# LFR_IR.net
KiCad netlist of a schematic drawn in Altium Designer
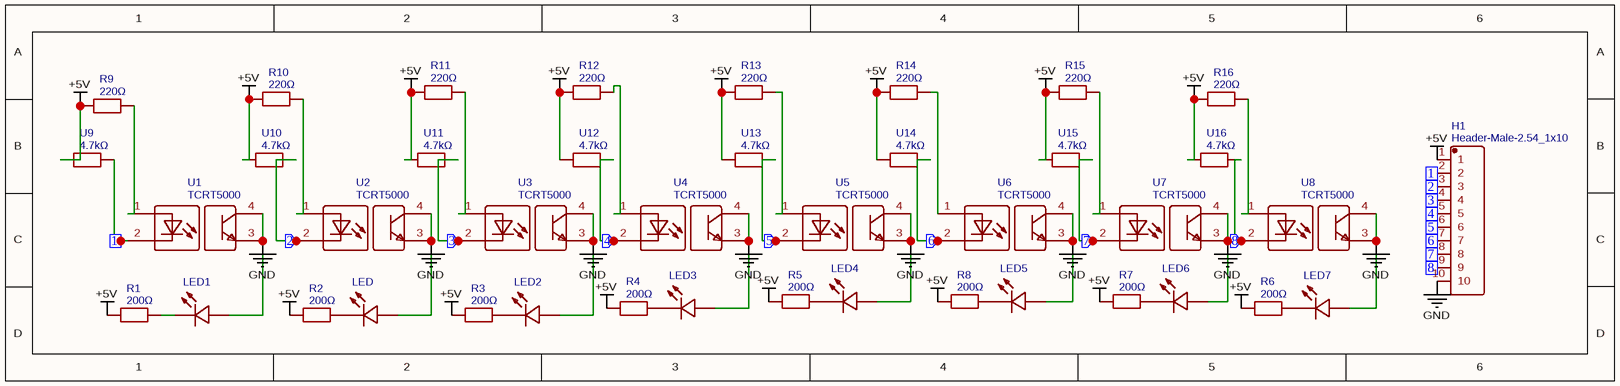
[diagram p0: LFR_IR.schdoc]

(export (version "E")
  (design (tool "Eeschema 10.0.6"))
  (components
    (comp (ref "H1")
      (value "Header-Male-2.54_1x10")
      (fields (field (name "MANUFACTURER PART") "2.54-1*10P针") (field (name "MANUFACTURER") "BOOMELE(博穆精密)"))
      (libsource (lib "altium-import") (part "root_0_Header-Male-2.54_1x10_"))
    )
    (comp (ref "LED")
      (value "LED-2835-白")
      (fields (field (name "CONTRIBUTOR") "LCSC"))
      (libsource (lib "altium-import") (part "root_0_LED-2835-白_"))
    )
    (comp (ref "LED1")
      (value "LED-2835-白")
      (fields (field (name "CONTRIBUTOR") "LCSC"))
      (libsource (lib "altium-import") (part "root_0_LED-2835-白_"))
    )
    (comp (ref "LED2")
      (value "LED-2835-白")
      (fields (field (name "CONTRIBUTOR") "LCSC"))
      (libsource (lib "altium-import") (part "root_0_LED-2835-白_"))
    )
    (comp (ref "LED3")
      (value "LED-2835-白")
      (fields (field (name "CONTRIBUTOR") "LCSC"))
      (libsource (lib "altium-import") (part "root_0_LED-2835-白_"))
    )
    (comp (ref "LED4")
      (value "LED-2835-白")
      (fields (field (name "CONTRIBUTOR") "LCSC"))
      (libsource (lib "altium-import") (part "root_0_LED-2835-白_"))
    )
    (comp (ref "LED5")
      (value "LED-2835-白")
      (fields (field (name "CONTRIBUTOR") "LCSC"))
      (libsource (lib "altium-import") (part "root_0_LED-2835-白_"))
    )
    (comp (ref "LED6")
      (value "LED-2835-白")
      (fields (field (name "CONTRIBUTOR") "LCSC"))
      (libsource (lib "altium-import") (part "root_0_LED-2835-白_"))
    )
    (comp (ref "LED7")
      (value "LED-2835-白")
      (fields (field (name "CONTRIBUTOR") "LCSC"))
      (libsource (lib "altium-import") (part "root_0_LED-2835-白_"))
    )
    (comp (ref "R1")
      (value "200Ω")
      (fields
        (field (name "MANUFACTURER") "VO(翔胜)")
        (field (name "MANUFACTURER PART") "CR1/4W-200Ω±5%-ST52")
        (field (name "CONTRIBUTOR") "lcsc")
      )
      (libsource (lib "altium-import") (part "root_0_200Ω_"))
    )
    (comp (ref "R2")
      (value "200Ω")
      (fields
        (field (name "MANUFACTURER") "VO(翔胜)")
        (field (name "MANUFACTURER PART") "CR1/4W-200Ω±5%-ST52")
        (field (name "CONTRIBUTOR") "lcsc")
      )
      (libsource (lib "altium-import") (part "root_0_200Ω_"))
    )
    (comp (ref "R3")
      (value "200Ω")
      (fields
        (field (name "MANUFACTURER") "VO(翔胜)")
        (field (name "MANUFACTURER PART") "CR1/4W-200Ω±5%-ST52")
        (field (name "CONTRIBUTOR") "lcsc")
      )
      (libsource (lib "altium-import") (part "root_0_200Ω_"))
    )
    (comp (ref "R4")
      (value "200Ω")
      (fields
        (field (name "MANUFACTURER") "VO(翔胜)")
        (field (name "MANUFACTURER PART") "CR1/4W-200Ω±5%-ST52")
        (field (name "CONTRIBUTOR") "lcsc")
      )
      (libsource (lib "altium-import") (part "root_0_200Ω_"))
    )
    (comp (ref "R5")
      (value "200Ω")
      (fields
        (field (name "MANUFACTURER") "VO(翔胜)")
        (field (name "MANUFACTURER PART") "CR1/4W-200Ω±5%-ST52")
        (field (name "CONTRIBUTOR") "lcsc")
      )
      (libsource (lib "altium-import") (part "root_0_200Ω_"))
    )
    (comp (ref "R6")
      (value "200Ω")
      (fields
        (field (name "MANUFACTURER") "VO(翔胜)")
        (field (name "MANUFACTURER PART") "CR1/4W-200Ω±5%-ST52")
        (field (name "CONTRIBUTOR") "lcsc")
      )
      (libsource (lib "altium-import") (part "root_0_200Ω_"))
    )
    (comp (ref "R7")
      (value "200Ω")
      (fields
        (field (name "MANUFACTURER") "VO(翔胜)")
        (field (name "MANUFACTURER PART") "CR1/4W-200Ω±5%-ST52")
        (field (name "CONTRIBUTOR") "lcsc")
      )
      (libsource (lib "altium-import") (part "root_0_200Ω_"))
    )
    (comp (ref "R8")
      (value "200Ω")
      (fields
        (field (name "MANUFACTURER") "VO(翔胜)")
        (field (name "MANUFACTURER PART") "CR1/4W-200Ω±5%-ST52")
        (field (name "CONTRIBUTOR") "lcsc")
      )
      (libsource (lib "altium-import") (part "root_0_200Ω_"))
    )
    (comp (ref "R9")
      (value "220Ω")
      (fields
        (field (name "MANUFACTURER") "VO(翔胜)")
        (field (name "MANUFACTURER PART") "CR1/4W-220Ω±5%-ST52")
        (field (name "CONTRIBUTOR") "lcsc")
      )
      (libsource (lib "altium-import") (part "root_0_220Ω_"))
    )
    (comp (ref "R10")
      (value "220Ω")
      (fields
        (field (name "MANUFACTURER") "VO(翔胜)")
        (field (name "MANUFACTURER PART") "CR1/4W-220Ω±5%-ST52")
        (field (name "CONTRIBUTOR") "lcsc")
      )
      (libsource (lib "altium-import") (part "root_0_220Ω_"))
    )
    (comp (ref "R11")
      (value "220Ω")
      (fields
        (field (name "MANUFACTURER") "VO(翔胜)")
        (field (name "MANUFACTURER PART") "CR1/4W-220Ω±5%-ST52")
        (field (name "CONTRIBUTOR") "lcsc")
      )
      (libsource (lib "altium-import") (part "root_0_220Ω_"))
    )
    (comp (ref "R12")
      (value "220Ω")
      (fields
        (field (name "MANUFACTURER") "VO(翔胜)")
        (field (name "MANUFACTURER PART") "CR1/4W-220Ω±5%-ST52")
        (field (name "CONTRIBUTOR") "lcsc")
      )
      (libsource (lib "altium-import") (part "root_0_220Ω_"))
    )
    (comp (ref "R13")
      (value "220Ω")
      (fields
        (field (name "MANUFACTURER") "VO(翔胜)")
        (field (name "MANUFACTURER PART") "CR1/4W-220Ω±5%-ST52")
        (field (name "CONTRIBUTOR") "lcsc")
      )
      (libsource (lib "altium-import") (part "root_0_220Ω_"))
    )
    (comp (ref "R14")
      (value "220Ω")
      (fields
        (field (name "MANUFACTURER") "VO(翔胜)")
        (field (name "MANUFACTURER PART") "CR1/4W-220Ω±5%-ST52")
        (field (name "CONTRIBUTOR") "lcsc")
      )
      (libsource (lib "altium-import") (part "root_0_220Ω_"))
    )
    (comp (ref "R15")
      (value "220Ω")
      (fields
        (field (name "MANUFACTURER") "VO(翔胜)")
        (field (name "MANUFACTURER PART") "CR1/4W-220Ω±5%-ST52")
        (field (name "CONTRIBUTOR") "lcsc")
      )
      (libsource (lib "altium-import") (part "root_0_220Ω_"))
    )
    (comp (ref "R16")
      (value "220Ω")
      (fields
        (field (name "MANUFACTURER") "VO(翔胜)")
        (field (name "MANUFACTURER PART") "CR1/4W-220Ω±5%-ST52")
        (field (name "CONTRIBUTOR") "lcsc")
      )
      (libsource (lib "altium-import") (part "root_0_220Ω_"))
    )
    (comp (ref "U1")
      (value "TCRT5000")
      (fields (field (name "MANUFACTURER") "VISHAY(威世)") (field (name "CONTRIBUTOR") "lcsc"))
      (libsource (lib "altium-import") (part "root_0_TCRT5000_"))
    )
    (comp (ref "U2")
      (value "TCRT5000")
      (fields (field (name "MANUFACTURER") "VISHAY(威世)") (field (name "CONTRIBUTOR") "lcsc"))
      (libsource (lib "altium-import") (part "root_0_TCRT5000_"))
    )
    (comp (ref "U3")
      (value "TCRT5000")
      (fields (field (name "MANUFACTURER") "VISHAY(威世)") (field (name "CONTRIBUTOR") "lcsc"))
      (libsource (lib "altium-import") (part "root_0_TCRT5000_"))
    )
    (comp (ref "U4")
      (value "TCRT5000")
      (fields (field (name "MANUFACTURER") "VISHAY(威世)") (field (name "CONTRIBUTOR") "lcsc"))
      (libsource (lib "altium-import") (part "root_0_TCRT5000_"))
    )
    (comp (ref "U5")
      (value "TCRT5000")
      (fields (field (name "MANUFACTURER") "VISHAY(威世)") (field (name "CONTRIBUTOR") "lcsc"))
      (libsource (lib "altium-import") (part "root_0_TCRT5000_"))
    )
    (comp (ref "U6")
      (value "TCRT5000")
      (fields (field (name "MANUFACTURER") "VISHAY(威世)") (field (name "CONTRIBUTOR") "lcsc"))
      (libsource (lib "altium-import") (part "root_0_TCRT5000_"))
    )
    (comp (ref "U7")
      (value "TCRT5000")
      (fields (field (name "MANUFACTURER") "VISHAY(威世)") (field (name "CONTRIBUTOR") "lcsc"))
      (libsource (lib "altium-import") (part "root_0_TCRT5000_"))
    )
    (comp (ref "U8")
      (value "TCRT5000")
      (fields (field (name "MANUFACTURER") "VISHAY(威世)") (field (name "CONTRIBUTOR") "lcsc"))
      (libsource (lib "altium-import") (part "root_0_TCRT5000_"))
    )
    (comp (ref "U9")
      (value "4.7kΩ")
      (fields
        (field (name "MANUFACTURER") "VO(翔胜)")
        (field (name "MANUFACTURER PART") "CR1/4W-4K7±5%-ST52")
        (field (name "CONTRIBUTOR") "lcsc")
      )
      (libsource (lib "altium-import") (part "root_0_4.7kΩ_"))
    )
    (comp (ref "U10")
      (value "4.7kΩ")
      (fields
        (field (name "MANUFACTURER") "VO(翔胜)")
        (field (name "MANUFACTURER PART") "CR1/4W-4K7±5%-ST52")
        (field (name "CONTRIBUTOR") "lcsc")
      )
      (libsource (lib "altium-import") (part "root_0_4.7kΩ_"))
    )
    (comp (ref "U11")
      (value "4.7kΩ")
      (fields
        (field (name "MANUFACTURER") "VO(翔胜)")
        (field (name "MANUFACTURER PART") "CR1/4W-4K7±5%-ST52")
        (field (name "CONTRIBUTOR") "lcsc")
      )
      (libsource (lib "altium-import") (part "root_0_4.7kΩ_"))
    )
    (comp (ref "U12")
      (value "4.7kΩ")
      (fields
        (field (name "MANUFACTURER") "VO(翔胜)")
        (field (name "MANUFACTURER PART") "CR1/4W-4K7±5%-ST52")
        (field (name "CONTRIBUTOR") "lcsc")
      )
      (libsource (lib "altium-import") (part "root_0_4.7kΩ_"))
    )
    (comp (ref "U13")
      (value "4.7kΩ")
      (fields
        (field (name "MANUFACTURER") "VO(翔胜)")
        (field (name "MANUFACTURER PART") "CR1/4W-4K7±5%-ST52")
        (field (name "CONTRIBUTOR") "lcsc")
      )
      (libsource (lib "altium-import") (part "root_0_4.7kΩ_"))
    )
    (comp (ref "U14")
      (value "4.7kΩ")
      (fields
        (field (name "MANUFACTURER") "VO(翔胜)")
        (field (name "MANUFACTURER PART") "CR1/4W-4K7±5%-ST52")
        (field (name "CONTRIBUTOR") "lcsc")
      )
      (libsource (lib "altium-import") (part "root_0_4.7kΩ_"))
    )
    (comp (ref "U15")
      (value "4.7kΩ")
      (fields
        (field (name "MANUFACTURER") "VO(翔胜)")
        (field (name "MANUFACTURER PART") "CR1/4W-4K7±5%-ST52")
        (field (name "CONTRIBUTOR") "lcsc")
      )
      (libsource (lib "altium-import") (part "root_0_4.7kΩ_"))
    )
    (comp (ref "U16")
      (value "4.7kΩ")
      (fields
        (field (name "MANUFACTURER") "VO(翔胜)")
        (field (name "MANUFACTURER PART") "CR1/4W-4K7±5%-ST52")
        (field (name "CONTRIBUTOR") "lcsc")
      )
      (libsource (lib "altium-import") (part "root_0_4.7kΩ_"))
    )
  )
  (nets
    (net (code "1") (name "+5V") (class "Default")
      (node (ref "H1") (pin "1") (pinfunction "1_1") (pintype "passive"))
      (node (ref "R1") (pin "1") (pinfunction "1_1") (pintype "passive"))
      (node (ref "R10") (pin "1") (pinfunction "1_1") (pintype "passive"))
      (node (ref "R11") (pin "1") (pinfunction "1_1") (pintype "passive"))
      (node (ref "R12") (pin "1") (pinfunction "1_1") (pintype "passive"))
      (node (ref "R13") (pin "1") (pinfunction "1_1") (pintype "passive"))
      (node (ref "R14") (pin "1") (pinfunction "1_1") (pintype "passive"))
      (node (ref "R15") (pin "1") (pinfunction "1_1") (pintype "passive"))
      (node (ref "R16") (pin "1") (pinfunction "1_1") (pintype "passive"))
      (node (ref "R2") (pin "1") (pinfunction "1_1") (pintype "passive"))
      (node (ref "R3") (pin "1") (pinfunction "1_1") (pintype "passive"))
      (node (ref "R4") (pin "1") (pinfunction "1_1") (pintype "passive"))
      (node (ref "R5") (pin "1") (pinfunction "1_1") (pintype "passive"))
      (node (ref "R6") (pin "1") (pinfunction "1_1") (pintype "passive"))
      (node (ref "R7") (pin "1") (pinfunction "1_1") (pintype "passive"))
      (node (ref "R8") (pin "1") (pinfunction "1_1") (pintype "passive"))
      (node (ref "R9") (pin "1") (pinfunction "1_1") (pintype "passive"))
      (node (ref "U10") (pin "1") (pinfunction "1_1") (pintype "passive"))
      (node (ref "U11") (pin "1") (pinfunction "1_1") (pintype "passive"))
      (node (ref "U12") (pin "1") (pinfunction "1_1") (pintype "passive"))
      (node (ref "U13") (pin "1") (pinfunction "1_1") (pintype "passive"))
      (node (ref "U14") (pin "1") (pinfunction "1_1") (pintype "passive"))
      (node (ref "U15") (pin "1") (pinfunction "1_1") (pintype "passive"))
      (node (ref "U16") (pin "1") (pinfunction "1_1") (pintype "passive"))
      (node (ref "U9") (pin "1") (pinfunction "1_1") (pintype "passive"))
    )
    (net (code "2") (name "/1") (class "Default")
      (node (ref "H1") (pin "2") (pinfunction "2_2") (pintype "passive"))
      (node (ref "U1") (pin "2") (pinfunction "2_2") (pintype "passive"))
      (node (ref "U9") (pin "2") (pinfunction "2_2") (pintype "passive"))
    )
    (net (code "3") (name "/2") (class "Default")
      (node (ref "H1") (pin "3") (pinfunction "3_3") (pintype "passive"))
      (node (ref "U10") (pin "2") (pinfunction "2_2") (pintype "passive"))
      (node (ref "U2") (pin "2") (pinfunction "2_2") (pintype "passive"))
    )
    (net (code "4") (name "/3") (class "Default")
      (node (ref "H1") (pin "4") (pinfunction "4_4") (pintype "passive"))
      (node (ref "U11") (pin "2") (pinfunction "2_2") (pintype "passive"))
      (node (ref "U3") (pin "2") (pinfunction "2_2") (pintype "passive"))
    )
    (net (code "5") (name "/4") (class "Default")
      (node (ref "H1") (pin "5") (pinfunction "5_5") (pintype "passive"))
      (node (ref "U12") (pin "2") (pinfunction "2_2") (pintype "passive"))
      (node (ref "U4") (pin "2") (pinfunction "2_2") (pintype "passive"))
    )
    (net (code "6") (name "/5") (class "Default")
      (node (ref "H1") (pin "6") (pinfunction "6_6") (pintype "passive"))
      (node (ref "U13") (pin "2") (pinfunction "2_2") (pintype "passive"))
      (node (ref "U5") (pin "2") (pinfunction "2_2") (pintype "passive"))
    )
    (net (code "7") (name "/6") (class "Default")
      (node (ref "H1") (pin "7") (pinfunction "7_7") (pintype "passive"))
      (node (ref "U14") (pin "2") (pinfunction "2_2") (pintype "passive"))
      (node (ref "U6") (pin "2") (pinfunction "2_2") (pintype "passive"))
    )
    (net (code "8") (name "/7") (class "Default")
      (node (ref "H1") (pin "8") (pinfunction "8_8") (pintype "passive"))
      (node (ref "U15") (pin "2") (pinfunction "2_2") (pintype "passive"))
      (node (ref "U7") (pin "2") (pinfunction "2_2") (pintype "passive"))
    )
    (net (code "9") (name "/8") (class "Default")
      (node (ref "H1") (pin "9") (pinfunction "9_9") (pintype "passive"))
      (node (ref "U16") (pin "2") (pinfunction "2_2") (pintype "passive"))
      (node (ref "U8") (pin "2") (pinfunction "2_2") (pintype "passive"))
    )
    (net (code "10") (name "GND") (class "Default")
      (node (ref "H1") (pin "10") (pinfunction "10_10") (pintype "passive"))
      (node (ref "LED") (pin "2") (pinfunction "A_2") (pintype "passive"))
      (node (ref "LED1") (pin "2") (pinfunction "A_2") (pintype "passive"))
      (node (ref "LED2") (pin "2") (pinfunction "A_2") (pintype "passive"))
      (node (ref "LED3") (pin "2") (pinfunction "A_2") (pintype "passive"))
      (node (ref "LED4") (pin "2") (pinfunction "A_2") (pintype "passive"))
      (node (ref "LED5") (pin "2") (pinfunction "A_2") (pintype "passive"))
      (node (ref "LED6") (pin "2") (pinfunction "A_2") (pintype "passive"))
      (node (ref "LED7") (pin "2") (pinfunction "A_2") (pintype "passive"))
      (node (ref "U1") (pin "3") (pinfunction "3_3") (pintype "passive"))
      (node (ref "U1") (pin "4") (pinfunction "4_4") (pintype "passive"))
      (node (ref "U2") (pin "3") (pinfunction "3_3") (pintype "passive"))
      (node (ref "U2") (pin "4") (pinfunction "4_4") (pintype "passive"))
      (node (ref "U3") (pin "3") (pinfunction "3_3") (pintype "passive"))
      (node (ref "U3") (pin "4") (pinfunction "4_4") (pintype "passive"))
      (node (ref "U4") (pin "3") (pinfunction "3_3") (pintype "passive"))
      (node (ref "U4") (pin "4") (pinfunction "4_4") (pintype "passive"))
      (node (ref "U5") (pin "3") (pinfunction "3_3") (pintype "passive"))
      (node (ref "U5") (pin "4") (pinfunction "4_4") (pintype "passive"))
      (node (ref "U6") (pin "3") (pinfunction "3_3") (pintype "passive"))
      (node (ref "U6") (pin "4") (pinfunction "4_4") (pintype "passive"))
      (node (ref "U7") (pin "3") (pinfunction "3_3") (pintype "passive"))
      (node (ref "U7") (pin "4") (pinfunction "4_4") (pintype "passive"))
      (node (ref "U8") (pin "3") (pinfunction "3_3") (pintype "passive"))
      (node (ref "U8") (pin "4") (pinfunction "4_4") (pintype "passive"))
    )
    (net (code "11") (name "Net-(LED-C)") (class "Default")
      (node (ref "LED") (pin "1") (pinfunction "C_1") (pintype "passive"))
      (node (ref "R2") (pin "2") (pinfunction "2_2") (pintype "passive"))
    )
    (net (code "12") (name "Net-(LED1-C)") (class "Default")
      (node (ref "LED1") (pin "1") (pinfunction "C_1") (pintype "passive"))
      (node (ref "R1") (pin "2") (pinfunction "2_2") (pintype "passive"))
    )
    (net (code "13") (name "Net-(LED2-C)") (class "Default")
      (node (ref "LED2") (pin "1") (pinfunction "C_1") (pintype "passive"))
      (node (ref "R3") (pin "2") (pinfunction "2_2") (pintype "passive"))
    )
    (net (code "14") (name "Net-(LED3-C)") (class "Default")
      (node (ref "LED3") (pin "1") (pinfunction "C_1") (pintype "passive"))
      (node (ref "R4") (pin "2") (pinfunction "2_2") (pintype "passive"))
    )
    (net (code "15") (name "Net-(LED4-C)") (class "Default")
      (node (ref "LED4") (pin "1") (pinfunction "C_1") (pintype "passive"))
      (node (ref "R5") (pin "2") (pinfunction "2_2") (pintype "passive"))
    )
    (net (code "16") (name "Net-(LED5-C)") (class "Default")
      (node (ref "LED5") (pin "1") (pinfunction "C_1") (pintype "passive"))
      (node (ref "R8") (pin "2") (pinfunction "2_2") (pintype "passive"))
    )
    (net (code "17") (name "Net-(LED6-C)") (class "Default")
      (node (ref "LED6") (pin "1") (pinfunction "C_1") (pintype "passive"))
      (node (ref "R7") (pin "2") (pinfunction "2_2") (pintype "passive"))
    )
    (net (code "18") (name "Net-(LED7-C)") (class "Default")
      (node (ref "LED7") (pin "1") (pinfunction "C_1") (pintype "passive"))
      (node (ref "R6") (pin "2") (pinfunction "2_2") (pintype "passive"))
    )
    (net (code "19") (name "Net-(R9-Pad2)") (class "Default")
      (node (ref "R9") (pin "2") (pinfunction "2_2") (pintype "passive"))
      (node (ref "U1") (pin "1") (pinfunction "1_1") (pintype "passive"))
    )
    (net (code "20") (name "Net-(R10-Pad2)") (class "Default")
      (node (ref "R10") (pin "2") (pinfunction "2_2") (pintype "passive"))
      (node (ref "U2") (pin "1") (pinfunction "1_1") (pintype "passive"))
    )
    (net (code "21") (name "Net-(R11-Pad2)") (class "Default")
      (node (ref "R11") (pin "2") (pinfunction "2_2") (pintype "passive"))
      (node (ref "U3") (pin "1") (pinfunction "1_1") (pintype "passive"))
    )
    (net (code "22") (name "Net-(R12-Pad2)") (class "Default")
      (node (ref "R12") (pin "2") (pinfunction "2_2") (pintype "passive"))
      (node (ref "U4") (pin "1") (pinfunction "1_1") (pintype "passive"))
    )
    (net (code "23") (name "Net-(R13-Pad2)") (class "Default")
      (node (ref "R13") (pin "2") (pinfunction "2_2") (pintype "passive"))
      (node (ref "U5") (pin "1") (pinfunction "1_1") (pintype "passive"))
    )
    (net (code "24") (name "Net-(R14-Pad2)") (class "Default")
      (node (ref "R14") (pin "2") (pinfunction "2_2") (pintype "passive"))
      (node (ref "U6") (pin "1") (pinfunction "1_1") (pintype "passive"))
    )
    (net (code "25") (name "Net-(R15-Pad2)") (class "Default")
      (node (ref "R15") (pin "2") (pinfunction "2_2") (pintype "passive"))
      (node (ref "U7") (pin "1") (pinfunction "1_1") (pintype "passive"))
    )
    (net (code "26") (name "Net-(R16-Pad2)") (class "Default")
      (node (ref "R16") (pin "2") (pinfunction "2_2") (pintype "passive"))
      (node (ref "U8") (pin "1") (pinfunction "1_1") (pintype "passive"))
    )
  )
)
